# 04_-_RAM.net
KiCad netlist of a schematic drawn in Altium Designer
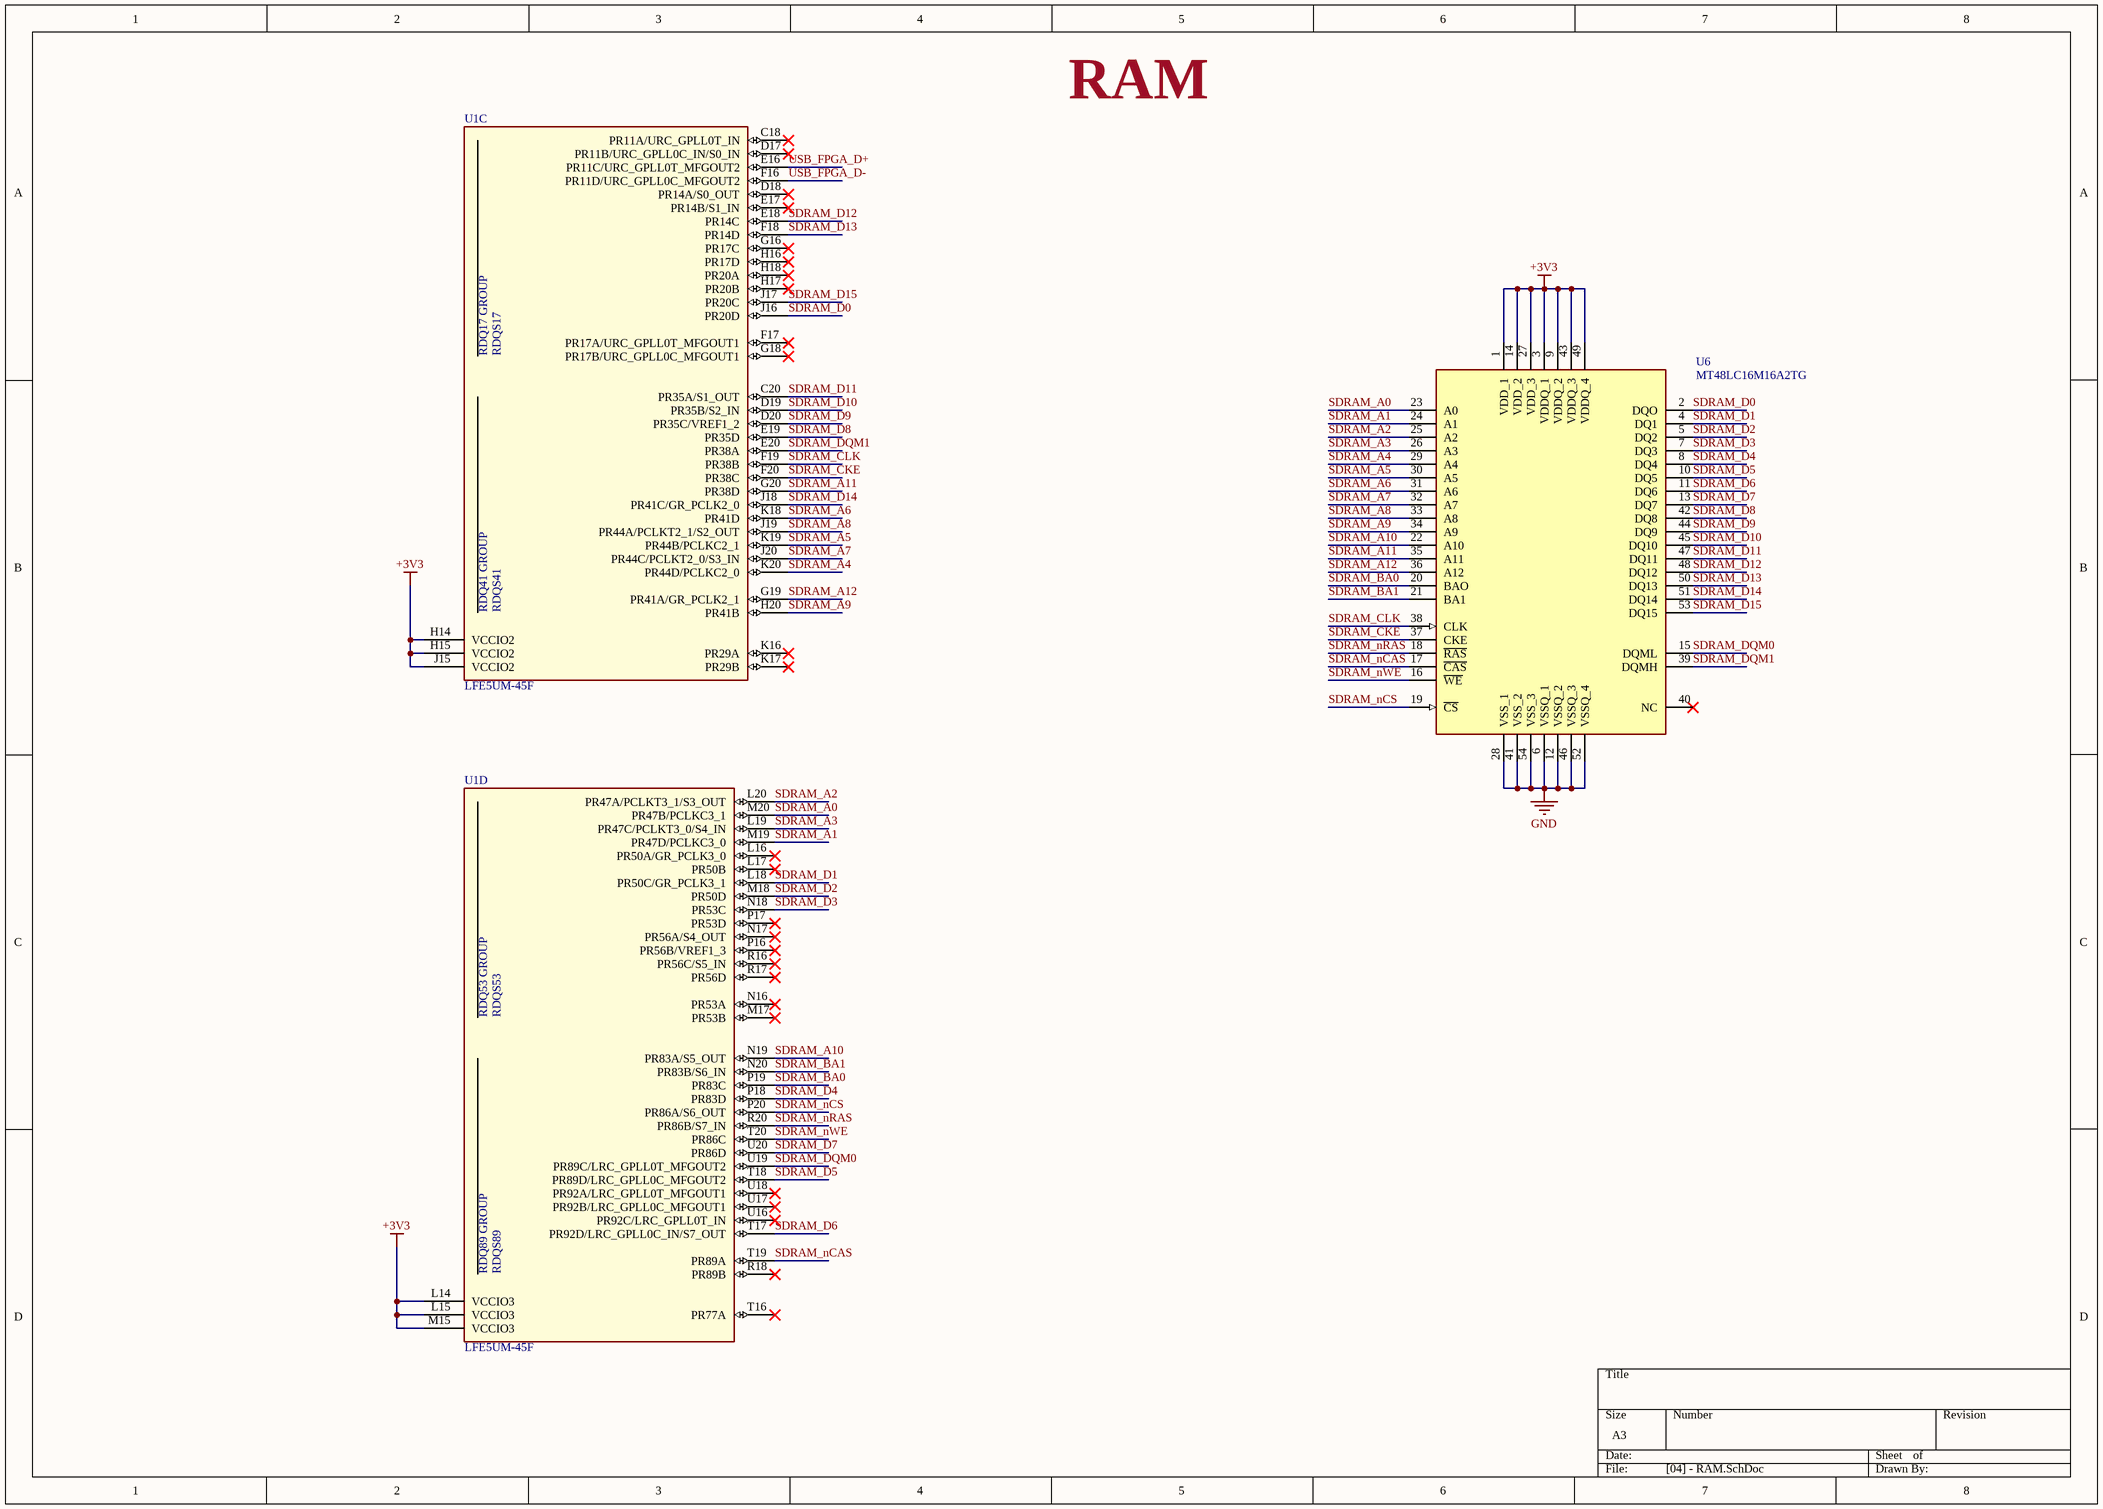
[diagram p0: [04] - RAM.SchDoc]

(export (version "E")
  (design (tool "Eeschema 10.0.6"))
  (components
    (comp (ref "U1")
      (value "LFE5UM-45F")
      (footprint "LFE5BG381")
      (description "ECP5 Series 44 K LUTs 203 I/O 1.1 V Slow Surface Mount FPGA - CABGA-381")
      (fields
        (field (name "MANUFACTURER") "Lattice Semiconductor")
        (field (name "MANUFACTURER PART NUMBER") "LFE5UM-45F-6BG381C")
      )
      (libsource (lib "ECP5_V2") (part "LFE5UM-45F-6BG381C"))
    )
    (comp (ref "U6")
      (value "MT48LC16M16A2TG")
      (footprint "SOP80P1176X120-54N")
      (description "IC Dram 256M Parallel 54TSOP")
      (fields
        (field (name "MANUFACTURER") "Alliance Memory")
        (field (name "MANUFACTURER PART NUMBER") "MT48LC16M16A2TG-6A:GTR")
      )
      (libsource (lib "ECP5_V2") (part "MT48LC16M16A2TG-6A{colon}GTR"))
    )
  )
  (nets
    (net (code "1") (name "+3V3") (class "Default")
      (node (ref "U1") (pin "H14") (pinfunction "VCCIO2_H14") (pintype "power_in"))
      (node (ref "U1") (pin "H15") (pinfunction "VCCIO2_H15") (pintype "power_in"))
      (node (ref "U1") (pin "J15") (pinfunction "VCCIO2_J15") (pintype "power_in"))
      (node (ref "U1") (pin "L14") (pinfunction "VCCIO3_L14") (pintype "power_in"))
      (node (ref "U1") (pin "L15") (pinfunction "VCCIO3_L15") (pintype "power_in"))
      (node (ref "U1") (pin "M15") (pinfunction "VCCIO3_M15") (pintype "power_in"))
      (node (ref "U6") (pin "1") (pinfunction "VDD_1_1") (pintype "power_in"))
      (node (ref "U6") (pin "14") (pinfunction "VDD_2_14") (pintype "power_in"))
      (node (ref "U6") (pin "27") (pinfunction "VDD_3_27") (pintype "power_in"))
      (node (ref "U6") (pin "3") (pinfunction "VDDQ_1_3") (pintype "power_in"))
      (node (ref "U6") (pin "43") (pinfunction "VDDQ_3_43") (pintype "power_in"))
      (node (ref "U6") (pin "49") (pinfunction "VDDQ_4_49") (pintype "power_in"))
      (node (ref "U6") (pin "9") (pinfunction "VDDQ_2_9") (pintype "power_in"))
    )
    (net (code "2") (name "/SDRAM_A0") (class "Default")
      (node (ref "U1") (pin "M20") (pinfunction "PR47B/PCLKC3_1_M20") (pintype "bidirectional"))
      (node (ref "U6") (pin "23") (pinfunction "A0_23") (pintype "passive"))
    )
    (net (code "3") (name "/SDRAM_A1") (class "Default")
      (node (ref "U1") (pin "M19") (pinfunction "PR47D/PCLKC3_0_M19") (pintype "bidirectional"))
      (node (ref "U6") (pin "24") (pinfunction "A1_24") (pintype "passive"))
    )
    (net (code "4") (name "/SDRAM_A2") (class "Default")
      (node (ref "U1") (pin "L20") (pinfunction "PR47A/PCLKT3_1/S3_OUT_L20") (pintype "bidirectional"))
      (node (ref "U6") (pin "25") (pinfunction "A2_25") (pintype "passive"))
    )
    (net (code "5") (name "/SDRAM_A3") (class "Default")
      (node (ref "U1") (pin "L19") (pinfunction "PR47C/PCLKT3_0/S4_IN_L19") (pintype "bidirectional"))
      (node (ref "U6") (pin "26") (pinfunction "A3_26") (pintype "passive"))
    )
    (net (code "6") (name "/SDRAM_A4") (class "Default")
      (node (ref "U1") (pin "K20") (pinfunction "PR44D/PCLKC2_0_K20") (pintype "bidirectional"))
      (node (ref "U6") (pin "29") (pinfunction "A4_29") (pintype "passive"))
    )
    (net (code "7") (name "/SDRAM_A5") (class "Default")
      (node (ref "U1") (pin "K19") (pinfunction "PR44B/PCLKC2_1_K19") (pintype "bidirectional"))
      (node (ref "U6") (pin "30") (pinfunction "A5_30") (pintype "passive"))
    )
    (net (code "8") (name "/SDRAM_A6") (class "Default")
      (node (ref "U1") (pin "K18") (pinfunction "PR41D_K18") (pintype "bidirectional"))
      (node (ref "U6") (pin "31") (pinfunction "A6_31") (pintype "passive"))
    )
    (net (code "9") (name "/SDRAM_A7") (class "Default")
      (node (ref "U1") (pin "J20") (pinfunction "PR44C/PCLKT2_0/S3_IN_J20") (pintype "bidirectional"))
      (node (ref "U6") (pin "32") (pinfunction "A7_32") (pintype "passive"))
    )
    (net (code "10") (name "/SDRAM_A8") (class "Default")
      (node (ref "U1") (pin "J19") (pinfunction "PR44A/PCLKT2_1/S2_OUT_J19") (pintype "bidirectional"))
      (node (ref "U6") (pin "33") (pinfunction "A8_33") (pintype "passive"))
    )
    (net (code "11") (name "/SDRAM_A9") (class "Default")
      (node (ref "U1") (pin "H20") (pinfunction "PR41B_H20") (pintype "bidirectional"))
      (node (ref "U6") (pin "34") (pinfunction "A9_34") (pintype "passive"))
    )
    (net (code "12") (name "/SDRAM_A10") (class "Default")
      (node (ref "U1") (pin "N19") (pinfunction "PR83A/S5_OUT_N19") (pintype "bidirectional"))
      (node (ref "U6") (pin "22") (pinfunction "A10_22") (pintype "passive"))
    )
    (net (code "13") (name "/SDRAM_A11") (class "Default")
      (node (ref "U1") (pin "G20") (pinfunction "PR38D_G20") (pintype "bidirectional"))
      (node (ref "U6") (pin "35") (pinfunction "A11_35") (pintype "passive"))
    )
    (net (code "14") (name "/SDRAM_A12") (class "Default")
      (node (ref "U1") (pin "G19") (pinfunction "PR41A/GR_PCLK2_1_G19") (pintype "bidirectional"))
      (node (ref "U6") (pin "36") (pinfunction "A12_36") (pintype "passive"))
    )
    (net (code "15") (name "/SDRAM_BA0") (class "Default")
      (node (ref "U1") (pin "P19") (pinfunction "PR83C_P19") (pintype "bidirectional"))
      (node (ref "U6") (pin "20") (pinfunction "BAO_20") (pintype "passive"))
    )
    (net (code "16") (name "/SDRAM_BA1") (class "Default")
      (node (ref "U1") (pin "N20") (pinfunction "PR83B/S6_IN_N20") (pintype "bidirectional"))
      (node (ref "U6") (pin "21") (pinfunction "BA1_21") (pintype "passive"))
    )
    (net (code "17") (name "/SDRAM_CKE") (class "Default")
      (node (ref "U1") (pin "F20") (pinfunction "PR38C_F20") (pintype "bidirectional"))
      (node (ref "U6") (pin "37") (pinfunction "CKE_37") (pintype "passive"))
    )
    (net (code "18") (name "/SDRAM_CLK") (class "Default")
      (node (ref "U1") (pin "F19") (pinfunction "PR38B_F19") (pintype "bidirectional"))
      (node (ref "U6") (pin "38") (pinfunction "CLK_38") (pintype "input"))
    )
    (net (code "19") (name "/SDRAM_D0") (class "Default")
      (node (ref "U1") (pin "J16") (pinfunction "PR20D_J16") (pintype "bidirectional"))
      (node (ref "U6") (pin "2") (pinfunction "DQO_2") (pintype "passive"))
    )
    (net (code "20") (name "/SDRAM_D1") (class "Default")
      (node (ref "U1") (pin "L18") (pinfunction "PR50C/GR_PCLK3_1_L18") (pintype "bidirectional"))
      (node (ref "U6") (pin "4") (pinfunction "DQ1_4") (pintype "passive"))
    )
    (net (code "21") (name "/SDRAM_D2") (class "Default")
      (node (ref "U1") (pin "M18") (pinfunction "PR50D_M18") (pintype "bidirectional"))
      (node (ref "U6") (pin "5") (pinfunction "DQ2_5") (pintype "passive"))
    )
    (net (code "22") (name "/SDRAM_D3") (class "Default")
      (node (ref "U1") (pin "N18") (pinfunction "PR53C_N18") (pintype "bidirectional"))
      (node (ref "U6") (pin "7") (pinfunction "DQ3_7") (pintype "passive"))
    )
    (net (code "23") (name "/SDRAM_D4") (class "Default")
      (node (ref "U1") (pin "P18") (pinfunction "PR83D_P18") (pintype "bidirectional"))
      (node (ref "U6") (pin "8") (pinfunction "DQ4_8") (pintype "passive"))
    )
    (net (code "24") (name "/SDRAM_D5") (class "Default")
      (node (ref "U1") (pin "T18") (pinfunction "PR89D/LRC_GPLL0C_MFGOUT2_T18") (pintype "bidirectional"))
      (node (ref "U6") (pin "10") (pinfunction "DQ5_10") (pintype "passive"))
    )
    (net (code "25") (name "/SDRAM_D6") (class "Default")
      (node (ref "U1") (pin "T17") (pinfunction "PR92D/LRC_GPLL0C_IN/S7_OUT_T17") (pintype "bidirectional"))
      (node (ref "U6") (pin "11") (pinfunction "DQ6_11") (pintype "passive"))
    )
    (net (code "26") (name "/SDRAM_D7") (class "Default")
      (node (ref "U1") (pin "U20") (pinfunction "PR86D_U20") (pintype "bidirectional"))
      (node (ref "U6") (pin "13") (pinfunction "DQ7_13") (pintype "passive"))
    )
    (net (code "27") (name "/SDRAM_D8") (class "Default")
      (node (ref "U1") (pin "E19") (pinfunction "PR35D_E19") (pintype "bidirectional"))
      (node (ref "U6") (pin "42") (pinfunction "DQ8_42") (pintype "passive"))
    )
    (net (code "28") (name "/SDRAM_D9") (class "Default")
      (node (ref "U1") (pin "D20") (pinfunction "PR35C/VREF1_2_D20") (pintype "bidirectional"))
      (node (ref "U6") (pin "44") (pinfunction "DQ9_44") (pintype "passive"))
    )
    (net (code "29") (name "/SDRAM_D10") (class "Default")
      (node (ref "U1") (pin "D19") (pinfunction "PR35B/S2_IN_D19") (pintype "bidirectional"))
      (node (ref "U6") (pin "45") (pinfunction "DQ10_45") (pintype "passive"))
    )
    (net (code "30") (name "/SDRAM_D11") (class "Default")
      (node (ref "U1") (pin "C20") (pinfunction "PR35A/S1_OUT_C20") (pintype "bidirectional"))
      (node (ref "U6") (pin "47") (pinfunction "DQ11_47") (pintype "passive"))
    )
    (net (code "31") (name "/SDRAM_D12") (class "Default")
      (node (ref "U1") (pin "E18") (pinfunction "PR14C_E18") (pintype "bidirectional"))
      (node (ref "U6") (pin "48") (pinfunction "DQ12_48") (pintype "passive"))
    )
    (net (code "32") (name "/SDRAM_D13") (class "Default")
      (node (ref "U1") (pin "F18") (pinfunction "PR14D_F18") (pintype "bidirectional"))
      (node (ref "U6") (pin "50") (pinfunction "DQ13_50") (pintype "passive"))
    )
    (net (code "33") (name "/SDRAM_D14") (class "Default")
      (node (ref "U1") (pin "J18") (pinfunction "PR41C/GR_PCLK2_0_J18") (pintype "bidirectional"))
      (node (ref "U6") (pin "51") (pinfunction "DQ14_51") (pintype "passive"))
    )
    (net (code "34") (name "/SDRAM_D15") (class "Default")
      (node (ref "U1") (pin "J17") (pinfunction "PR20C_J17") (pintype "bidirectional"))
      (node (ref "U6") (pin "53") (pinfunction "DQ15_53") (pintype "passive"))
    )
    (net (code "35") (name "/SDRAM_DQM0") (class "Default")
      (node (ref "U1") (pin "U19") (pinfunction "PR89C/LRC_GPLL0T_MFGOUT2_U19") (pintype "bidirectional"))
      (node (ref "U6") (pin "15") (pinfunction "DQML_15") (pintype "passive"))
    )
    (net (code "36") (name "/SDRAM_DQM1") (class "Default")
      (node (ref "U1") (pin "E20") (pinfunction "PR38A_E20") (pintype "bidirectional"))
      (node (ref "U6") (pin "39") (pinfunction "DQMH_39") (pintype "passive"))
    )
    (net (code "37") (name "/SDRAM_nCAS") (class "Default")
      (node (ref "U1") (pin "T19") (pinfunction "PR89A_T19") (pintype "bidirectional"))
      (node (ref "U6") (pin "17") (pinfunction "~{CAS}_17") (pintype "passive"))
    )
    (net (code "38") (name "/SDRAM_nCS") (class "Default")
      (node (ref "U1") (pin "P20") (pinfunction "PR86A/S6_OUT_P20") (pintype "bidirectional"))
      (node (ref "U6") (pin "19") (pinfunction "~{CS}_19") (pintype "input"))
    )
    (net (code "39") (name "/SDRAM_nRAS") (class "Default")
      (node (ref "U1") (pin "R20") (pinfunction "PR86B/S7_IN_R20") (pintype "bidirectional"))
      (node (ref "U6") (pin "18") (pinfunction "~{RAS}_18") (pintype "passive"))
    )
    (net (code "40") (name "/SDRAM_nWE") (class "Default")
      (node (ref "U1") (pin "T20") (pinfunction "PR86C_T20") (pintype "bidirectional"))
      (node (ref "U6") (pin "16") (pinfunction "~{WE}_16") (pintype "passive"))
    )
    (net (code "41") (name "/USB_FPGA_D+") (class "Default")
      (node (ref "U1") (pin "E16") (pinfunction "PR11C/URC_GPLL0T_MFGOUT2_E16") (pintype "bidirectional"))
    )
    (net (code "42") (name "/USB_FPGA_D-") (class "Default")
      (node (ref "U1") (pin "F16") (pinfunction "PR11D/URC_GPLL0C_MFGOUT2_F16") (pintype "bidirectional"))
    )
    (net (code "43") (name "GND") (class "Default")
      (node (ref "U6") (pin "12") (pinfunction "VSSQ_2_12") (pintype "power_in"))
      (node (ref "U6") (pin "28") (pinfunction "VSS_1_28") (pintype "power_in"))
      (node (ref "U6") (pin "41") (pinfunction "VSS_2_41") (pintype "power_in"))
      (node (ref "U6") (pin "46") (pinfunction "VSSQ_3_46") (pintype "power_in"))
      (node (ref "U6") (pin "52") (pinfunction "VSSQ_4_52") (pintype "power_in"))
      (node (ref "U6") (pin "54") (pinfunction "VSS_3_54") (pintype "power_in"))
      (node (ref "U6") (pin "6") (pinfunction "VSSQ_1_6") (pintype "power_in"))
    )
    (net (code "44") (name "unconnected-(U1C-PR11A{slash}URC_GPLL0T_IN-PadC18)") (class "Default")
      (node (ref "U1") (pin "C18") (pinfunction "PR11A/URC_GPLL0T_IN_C18") (pintype "bidirectional+no_connect"))
    )
    (net (code "45") (name "unconnected-(U1C-PR11B{slash}URC_GPLL0C_IN{slash}S0_IN-PadD17)") (class "Default")
      (node (ref "U1") (pin "D17") (pinfunction "PR11B/URC_GPLL0C_IN/S0_IN_D17") (pintype "bidirectional+no_connect"))
    )
    (net (code "46") (name "unconnected-(U1C-PR14A{slash}S0_OUT-PadD18)") (class "Default")
      (node (ref "U1") (pin "D18") (pinfunction "PR14A/S0_OUT_D18") (pintype "bidirectional+no_connect"))
    )
    (net (code "47") (name "unconnected-(U1C-PR14B{slash}S1_IN-PadE17)") (class "Default")
      (node (ref "U1") (pin "E17") (pinfunction "PR14B/S1_IN_E17") (pintype "bidirectional+no_connect"))
    )
    (net (code "48") (name "unconnected-(U1C-PR17A{slash}URC_GPLL0T_MFGOUT1-PadF17)") (class "Default")
      (node (ref "U1") (pin "F17") (pinfunction "PR17A/URC_GPLL0T_MFGOUT1_F17") (pintype "bidirectional+no_connect"))
    )
    (net (code "49") (name "unconnected-(U1C-PR17B{slash}URC_GPLL0C_MFGOUT1-PadG18)") (class "Default")
      (node (ref "U1") (pin "G18") (pinfunction "PR17B/URC_GPLL0C_MFGOUT1_G18") (pintype "bidirectional+no_connect"))
    )
    (net (code "50") (name "unconnected-(U1C-PR17C-PadG16)") (class "Default")
      (node (ref "U1") (pin "G16") (pinfunction "PR17C_G16") (pintype "bidirectional+no_connect"))
    )
    (net (code "51") (name "unconnected-(U1C-PR17D-PadH16)") (class "Default")
      (node (ref "U1") (pin "H16") (pinfunction "PR17D_H16") (pintype "bidirectional+no_connect"))
    )
    (net (code "52") (name "unconnected-(U1C-PR20A-PadH18)") (class "Default")
      (node (ref "U1") (pin "H18") (pinfunction "PR20A_H18") (pintype "bidirectional+no_connect"))
    )
    (net (code "53") (name "unconnected-(U1C-PR20B-PadH17)") (class "Default")
      (node (ref "U1") (pin "H17") (pinfunction "PR20B_H17") (pintype "bidirectional+no_connect"))
    )
    (net (code "54") (name "unconnected-(U1C-PR29A-PadK16)") (class "Default")
      (node (ref "U1") (pin "K16") (pinfunction "PR29A_K16") (pintype "bidirectional+no_connect"))
    )
    (net (code "55") (name "unconnected-(U1C-PR29B-PadK17)") (class "Default")
      (node (ref "U1") (pin "K17") (pinfunction "PR29B_K17") (pintype "bidirectional+no_connect"))
    )
    (net (code "56") (name "unconnected-(U1D-PR50A{slash}GR_PCLK3_0-PadL16)") (class "Default")
      (node (ref "U1") (pin "L16") (pinfunction "PR50A/GR_PCLK3_0_L16") (pintype "bidirectional+no_connect"))
    )
    (net (code "57") (name "unconnected-(U1D-PR50B-PadL17)") (class "Default")
      (node (ref "U1") (pin "L17") (pinfunction "PR50B_L17") (pintype "bidirectional+no_connect"))
    )
    (net (code "58") (name "unconnected-(U1D-PR53A-PadN16)") (class "Default")
      (node (ref "U1") (pin "N16") (pinfunction "PR53A_N16") (pintype "bidirectional+no_connect"))
    )
    (net (code "59") (name "unconnected-(U1D-PR53B-PadM17)") (class "Default")
      (node (ref "U1") (pin "M17") (pinfunction "PR53B_M17") (pintype "bidirectional+no_connect"))
    )
    (net (code "60") (name "unconnected-(U1D-PR53D-PadP17)") (class "Default")
      (node (ref "U1") (pin "P17") (pinfunction "PR53D_P17") (pintype "bidirectional+no_connect"))
    )
    (net (code "61") (name "unconnected-(U1D-PR56A{slash}S4_OUT-PadN17)") (class "Default")
      (node (ref "U1") (pin "N17") (pinfunction "PR56A/S4_OUT_N17") (pintype "bidirectional+no_connect"))
    )
    (net (code "62") (name "unconnected-(U1D-PR56B{slash}VREF1_3-PadP16)") (class "Default")
      (node (ref "U1") (pin "P16") (pinfunction "PR56B/VREF1_3_P16") (pintype "bidirectional+no_connect"))
    )
    (net (code "63") (name "unconnected-(U1D-PR56C{slash}S5_IN-PadR16)") (class "Default")
      (node (ref "U1") (pin "R16") (pinfunction "PR56C/S5_IN_R16") (pintype "bidirectional+no_connect"))
    )
    (net (code "64") (name "unconnected-(U1D-PR56D-PadR17)") (class "Default")
      (node (ref "U1") (pin "R17") (pinfunction "PR56D_R17") (pintype "bidirectional+no_connect"))
    )
    (net (code "65") (name "unconnected-(U1D-PR77A-PadT16)") (class "Default")
      (node (ref "U1") (pin "T16") (pinfunction "PR77A_T16") (pintype "bidirectional+no_connect"))
    )
    (net (code "66") (name "unconnected-(U1D-PR89B-PadR18)") (class "Default")
      (node (ref "U1") (pin "R18") (pinfunction "PR89B_R18") (pintype "bidirectional+no_connect"))
    )
    (net (code "67") (name "unconnected-(U1D-PR92A{slash}LRC_GPLL0T_MFGOUT1-PadU18)") (class "Default")
      (node (ref "U1") (pin "U18") (pinfunction "PR92A/LRC_GPLL0T_MFGOUT1_U18") (pintype "bidirectional+no_connect"))
    )
    (net (code "68") (name "unconnected-(U1D-PR92B{slash}LRC_GPLL0C_MFGOUT1-PadU17)") (class "Default")
      (node (ref "U1") (pin "U17") (pinfunction "PR92B/LRC_GPLL0C_MFGOUT1_U17") (pintype "bidirectional+no_connect"))
    )
    (net (code "69") (name "unconnected-(U1D-PR92C{slash}LRC_GPLL0T_IN-PadU16)") (class "Default")
      (node (ref "U1") (pin "U16") (pinfunction "PR92C/LRC_GPLL0T_IN_U16") (pintype "bidirectional+no_connect"))
    )
    (net (code "70") (name "unconnected-(U6-NC-Pad40)") (class "Default")
      (node (ref "U6") (pin "40") (pinfunction "NC_40") (pintype "passive+no_connect"))
    )
  )
)
